# remote.net
KiCad netlist of a schematic drawn in EAGLE
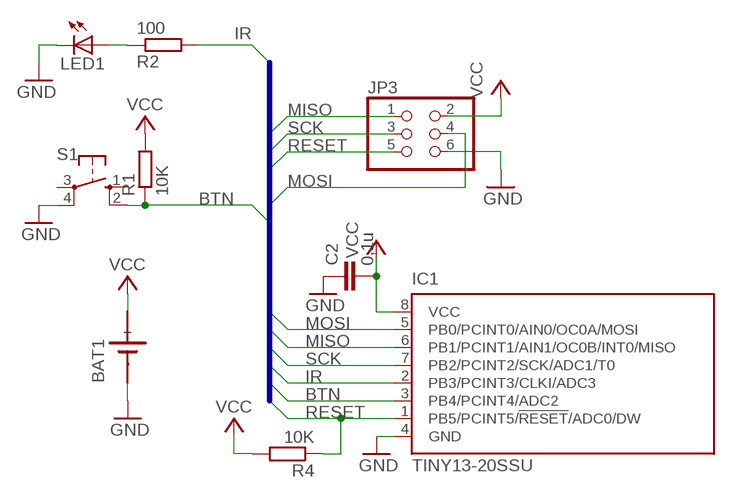
[diagram p0: schematic, sheet 1]

(export (version "E")
  (design (tool "Eeschema 10.0.6"))
  (components
    (comp (ref "BAT1")
      (value "SN2032")
      (footprint "eagle-import:SN2032")
      (libsource (lib "eagle-import") (part "SN2032"))
    )
    (comp (ref "C2")
      (value "0,1u")
      (footprint "eagle-import:C1206")
      (libsource (lib "eagle-import") (part "C-EUC1206"))
    )
    (comp (ref "IC1")
      (value "TINY13-20SSU")
      (footprint "eagle-import:8S1")
      (fields (field (name "MPN") "ATTINY13-20SSU"))
      (libsource (lib "eagle-import") (part "TINY13SSU-20"))
    )
    (comp (ref "JP3")
      (value "PINHD-2X3_2.54")
      (footprint "eagle-import:2X03")
      (libsource (lib "eagle-import") (part "PINHD-2X3_2.54"))
    )
    (comp (ref "LED1")
      (value "LED3MM")
      (footprint "eagle-import:LED3MM")
      (libsource (lib "eagle-import") (part "LED3MM"))
    )
    (comp (ref "R1")
      (value "10K")
      (footprint "eagle-import:R1206")
      (libsource (lib "eagle-import") (part "R-EU_R1206"))
    )
    (comp (ref "R2")
      (value "100")
      (footprint "eagle-import:R1206")
      (libsource (lib "eagle-import") (part "R-EU_R1206"))
    )
    (comp (ref "R4")
      (value "10K")
      (footprint "eagle-import:R1206")
      (libsource (lib "eagle-import") (part "R-EU_R1206"))
    )
    (comp (ref "S1")
      (value "10-XX")
      (footprint "eagle-import:B3F-10XX")
      (fields (field (name "MPN") "B3F-1000"))
      (libsource (lib "eagle-import") (part "10-XX"))
    )
  )
  (nets
    (net (code "1") (name "/BTN") (class "Default")
      (node (ref "IC1") (pin "3") (pinfunction "PB4/PCINT4/ADC2_3") (pintype "bidirectional"))
      (node (ref "R1") (pin "1") (pinfunction "1_1") (pintype "passive"))
      (node (ref "S1") (pin "2") (pinfunction "S1_2") (pintype "passive"))
    )
    (net (code "2") (name "/IR") (class "Default")
      (node (ref "IC1") (pin "2") (pinfunction "PB3/PCINT3/CLKI/ADC3_2") (pintype "bidirectional"))
      (node (ref "R2") (pin "2") (pinfunction "2_2") (pintype "passive"))
    )
    (net (code "3") (name "/MISO") (class "Default")
      (node (ref "IC1") (pin "6") (pinfunction "PB1/PCINT1/AIN1/OC0B/INT0/MISO_6") (pintype "bidirectional"))
      (node (ref "JP3") (pin "1") (pinfunction "1_1") (pintype "passive"))
    )
    (net (code "4") (name "/MOSI") (class "Default")
      (node (ref "IC1") (pin "5") (pinfunction "PB0/PCINT0/AIN0/OC0A/MOSI_5") (pintype "bidirectional"))
      (node (ref "JP3") (pin "4") (pinfunction "4_4") (pintype "passive"))
    )
    (net (code "5") (name "/RESET") (class "Default")
      (node (ref "IC1") (pin "1") (pinfunction "PB5/PCINT5/~{RESET}/ADC0/DW_1") (pintype "bidirectional"))
      (node (ref "JP3") (pin "5") (pinfunction "5_5") (pintype "passive"))
      (node (ref "R4") (pin "1") (pinfunction "1_1") (pintype "passive"))
    )
    (net (code "6") (name "/SCK") (class "Default")
      (node (ref "IC1") (pin "7") (pinfunction "PB2/PCINT2/SCK/ADC1/T0_7") (pintype "bidirectional"))
      (node (ref "JP3") (pin "3") (pinfunction "3_3") (pintype "passive"))
    )
    (net (code "7") (name "GND") (class "Default")
      (node (ref "BAT1") (pin "-") (pinfunction "-_-") (pintype "passive"))
      (node (ref "C2") (pin "1") (pinfunction "1_1") (pintype "passive"))
      (node (ref "IC1") (pin "4") (pinfunction "GND_4") (pintype "power_in"))
      (node (ref "JP3") (pin "6") (pinfunction "6_6") (pintype "passive"))
      (node (ref "LED1") (pin "K") (pinfunction "C_K") (pintype "passive"))
      (node (ref "S1") (pin "4") (pinfunction "P1_4") (pintype "passive"))
    )
    (net (code "8") (name "Net-(LED1-PadA)") (class "Default")
      (node (ref "LED1") (pin "A") (pinfunction "A_A") (pintype "passive"))
      (node (ref "R2") (pin "1") (pinfunction "1_1") (pintype "passive"))
    )
    (net (code "9") (name "VCC") (class "Default")
      (node (ref "BAT1") (pin "+") (pinfunction "+_+") (pintype "passive"))
      (node (ref "C2") (pin "2") (pinfunction "2_2") (pintype "passive"))
      (node (ref "IC1") (pin "8") (pinfunction "VCC_8") (pintype "power_in"))
      (node (ref "JP3") (pin "2") (pinfunction "2_2") (pintype "passive"))
      (node (ref "R1") (pin "2") (pinfunction "2_2") (pintype "passive"))
      (node (ref "R4") (pin "2") (pinfunction "2_2") (pintype "passive"))
    )
    (net (code "10") (name "unconnected-(S1-P-Pad3)") (class "Default")
      (node (ref "S1") (pin "3") (pinfunction "P_3") (pintype "passive"))
    )
    (net (code "11") (name "unconnected-(S1-S-Pad1)") (class "Default")
      (node (ref "S1") (pin "1") (pinfunction "S_1") (pintype "passive"))
    )
  )
)
